# Thermostat.net
KiCad netlist of a schematic drawn in EAGLE
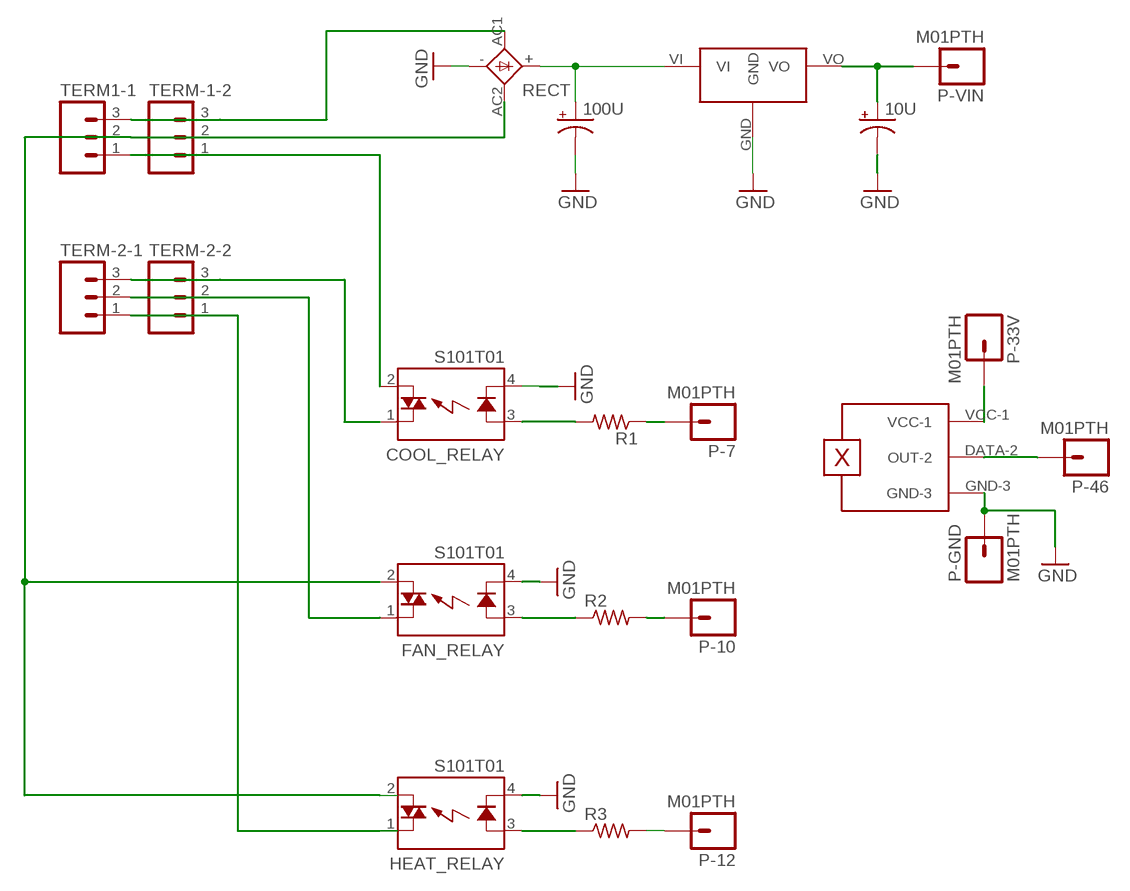
[diagram p0: schematic, sheet 1]

(export (version "E")
  (design (tool "Eeschema 10.0.6"))
  (components
    (comp (ref "10U")
      (value "CAP_POLPTH2")
      (footprint "eagle-import:CPOL-RADIAL-10UF-25V")
      (libsource (lib "eagle-import") (part "CAP_POLPTH2"))
    )
    (comp (ref "100U")
      (value "CAP_POLPTH1")
      (footprint "eagle-import:CPOL-RADIAL-100UF-25V")
      (libsource (lib "eagle-import") (part "CAP_POLPTH1"))
    )
    (comp (ref "COOL_RELAY")
      (value "S101T01")
      (footprint "eagle-import:S102T0X")
      (fields (field (name "OC_FARNELL") "unknown") (field (name "OC_NEWARK") "unknown"))
      (libsource (lib "eagle-import") (part "S?101T01"))
    )
    (comp (ref "FAN_RELAY")
      (value "S101T01")
      (footprint "eagle-import:S102T0X")
      (fields (field (name "OC_FARNELL") "unknown") (field (name "OC_NEWARK") "unknown"))
      (libsource (lib "eagle-import") (part "S?101T01"))
    )
    (comp (ref "HEAT_RELAY")
      (value "S101T01")
      (footprint "eagle-import:S102T0X")
      (fields (field (name "OC_FARNELL") "unknown") (field (name "OC_NEWARK") "unknown"))
      (libsource (lib "eagle-import") (part "S?101T01"))
    )
    (comp (ref "P-7")
      (value "M01PTH")
      (footprint "eagle-import:1X01")
      (libsource (lib "eagle-import") (part "M01PTH"))
    )
    (comp (ref "P-10")
      (value "M01PTH")
      (footprint "eagle-import:1X01")
      (libsource (lib "eagle-import") (part "M01PTH"))
    )
    (comp (ref "P-12")
      (value "M01PTH")
      (footprint "eagle-import:1X01")
      (libsource (lib "eagle-import") (part "M01PTH"))
    )
    (comp (ref "P-33V")
      (value "M01PTH")
      (footprint "eagle-import:1X01")
      (libsource (lib "eagle-import") (part "M01PTH"))
    )
    (comp (ref "P-46")
      (value "M01PTH")
      (footprint "eagle-import:1X01")
      (libsource (lib "eagle-import") (part "M01PTH"))
    )
    (comp (ref "P-GND")
      (value "M01PTH")
      (footprint "eagle-import:1X01")
      (libsource (lib "eagle-import") (part "M01PTH"))
    )
    (comp (ref "P-VIN")
      (value "M01PTH")
      (footprint "eagle-import:1X01")
      (libsource (lib "eagle-import") (part "M01PTH"))
    )
    (comp (ref "R1")
      (value "R-US_0204/2V")
      (footprint "eagle-import:0204V")
      (libsource (lib "eagle-import") (part "R-US_0204/2V"))
    )
    (comp (ref "R2")
      (value "R-US_0204/2V")
      (footprint "eagle-import:0204V")
      (libsource (lib "eagle-import") (part "R-US_0204/2V"))
    )
    (comp (ref "R3")
      (value "R-US_0204/2V")
      (footprint "eagle-import:0204V")
      (libsource (lib "eagle-import") (part "R-US_0204/2V"))
    )
    (comp (ref "RECT")
      (value "GBU4")
      (footprint "eagle-import:GBU4S")
      (libsource (lib "eagle-import") (part "GBU4"))
    )
    (comp (ref "TERM-1-2")
      (value "M031X03_NO_SILK")
      (footprint "eagle-import:1X03_NO_SILK")
      (libsource (lib "eagle-import") (part "M031X03_NO_SILK"))
    )
    (comp (ref "TERM-2-1")
      (value "M031X03_NO_SILK")
      (footprint "eagle-import:1X03_NO_SILK")
      (libsource (lib "eagle-import") (part "M031X03_NO_SILK"))
    )
    (comp (ref "TERM-2-2")
      (value "M031X03_NO_SILK")
      (footprint "eagle-import:1X03_NO_SILK")
      (libsource (lib "eagle-import") (part "M031X03_NO_SILK"))
    )
    (comp (ref "TERM1-1")
      (value "M031X03_NO_SILK")
      (footprint "eagle-import:1X03_NO_SILK")
      (libsource (lib "eagle-import") (part "M031X03_NO_SILK"))
    )
    (comp (ref "U$1")
      (value "TMP36")
      (footprint "eagle-import:TMP36")
      (libsource (lib "eagle-import") (part "TMP36"))
    )
    (comp (ref "U$2")
      (value "V715W-500R")
      (footprint "eagle-import:SWITCHINGREGULATOR")
      (libsource (lib "eagle-import") (part "V715W-500R"))
    )
  )
  (nets
    (net (code "1") (name "GND") (class "Default")
      (node (ref "100U") (pin "2") (pinfunction "-_2") (pintype "passive"))
      (node (ref "10U") (pin "2") (pinfunction "-_2") (pintype "passive"))
      (node (ref "COOL_RELAY") (pin "4") (pinfunction "K_4") (pintype "passive"))
      (node (ref "FAN_RELAY") (pin "4") (pinfunction "K_4") (pintype "passive"))
      (node (ref "HEAT_RELAY") (pin "4") (pinfunction "K_4") (pintype "passive"))
      (node (ref "P-GND") (pin "1") (pinfunction "1_1") (pintype "passive"))
      (node (ref "RECT") (pin "-") (pinfunction "-_-") (pintype "passive"))
      (node (ref "U$1") (pin "GND-3") (pinfunction "GND-3_GND-3") (pintype "bidirectional"))
      (node (ref "U$2") (pin "GND") (pinfunction "GND_GND") (pintype "bidirectional"))
    )
    (net (code "2") (name "Net-(10U-+)") (class "Default")
      (node (ref "10U") (pin "1") (pinfunction "+_1") (pintype "passive"))
      (node (ref "P-VIN") (pin "1") (pinfunction "1_1") (pintype "passive"))
      (node (ref "U$2") (pin "VO") (pinfunction "VO_VO") (pintype "bidirectional"))
    )
    (net (code "3") (name "Net-(100U-+)") (class "Default")
      (node (ref "100U") (pin "1") (pinfunction "+_1") (pintype "passive"))
      (node (ref "RECT") (pin "+") (pinfunction "+_+") (pintype "passive"))
      (node (ref "U$2") (pin "VI") (pinfunction "VI_VI") (pintype "bidirectional"))
    )
    (net (code "4") (name "Net-(COOL_RELAY-A)") (class "Default")
      (node (ref "COOL_RELAY") (pin "3") (pinfunction "A_3") (pintype "passive"))
      (node (ref "R1") (pin "2") (pinfunction "2_2") (pintype "passive"))
    )
    (net (code "5") (name "Net-(COOL_RELAY-DS1)") (class "Default")
      (node (ref "COOL_RELAY") (pin "1") (pinfunction "DS1_1") (pintype "passive"))
      (node (ref "TERM-2-1") (pin "3") (pinfunction "3_3") (pintype "passive"))
      (node (ref "TERM-2-2") (pin "3") (pinfunction "3_3") (pintype "passive"))
    )
    (net (code "6") (name "Net-(COOL_RELAY-DS2)") (class "Default")
      (node (ref "COOL_RELAY") (pin "2") (pinfunction "DS2_2") (pintype "passive"))
      (node (ref "TERM-1-2") (pin "1") (pinfunction "1_1") (pintype "passive"))
      (node (ref "TERM1-1") (pin "1") (pinfunction "1_1") (pintype "passive"))
    )
    (net (code "7") (name "Net-(FAN_RELAY-A)") (class "Default")
      (node (ref "FAN_RELAY") (pin "3") (pinfunction "A_3") (pintype "passive"))
      (node (ref "R2") (pin "1") (pinfunction "1_1") (pintype "passive"))
    )
    (net (code "8") (name "Net-(FAN_RELAY-DS1)") (class "Default")
      (node (ref "FAN_RELAY") (pin "1") (pinfunction "DS1_1") (pintype "passive"))
      (node (ref "TERM-2-1") (pin "2") (pinfunction "2_2") (pintype "passive"))
      (node (ref "TERM-2-2") (pin "2") (pinfunction "2_2") (pintype "passive"))
    )
    (net (code "9") (name "Net-(FAN_RELAY-DS2)") (class "Default")
      (node (ref "FAN_RELAY") (pin "2") (pinfunction "DS2_2") (pintype "passive"))
      (node (ref "HEAT_RELAY") (pin "2") (pinfunction "DS2_2") (pintype "passive"))
      (node (ref "RECT") (pin "AC2") (pinfunction "AC1_AC2") (pintype "passive"))
      (node (ref "TERM-1-2") (pin "2") (pinfunction "2_2") (pintype "passive"))
      (node (ref "TERM1-1") (pin "2") (pinfunction "2_2") (pintype "passive"))
    )
    (net (code "10") (name "Net-(HEAT_RELAY-A)") (class "Default")
      (node (ref "HEAT_RELAY") (pin "3") (pinfunction "A_3") (pintype "passive"))
      (node (ref "R3") (pin "1") (pinfunction "1_1") (pintype "passive"))
    )
    (net (code "11") (name "Net-(HEAT_RELAY-DS1)") (class "Default")
      (node (ref "HEAT_RELAY") (pin "1") (pinfunction "DS1_1") (pintype "passive"))
      (node (ref "TERM-2-1") (pin "1") (pinfunction "1_1") (pintype "passive"))
      (node (ref "TERM-2-2") (pin "1") (pinfunction "1_1") (pintype "passive"))
    )
    (net (code "12") (name "Net-(P-7-Pad1)") (class "Default")
      (node (ref "P-7") (pin "1") (pinfunction "1_1") (pintype "passive"))
      (node (ref "R1") (pin "1") (pinfunction "1_1") (pintype "passive"))
    )
    (net (code "13") (name "Net-(P-10-Pad1)") (class "Default")
      (node (ref "P-10") (pin "1") (pinfunction "1_1") (pintype "passive"))
      (node (ref "R2") (pin "2") (pinfunction "2_2") (pintype "passive"))
    )
    (net (code "14") (name "Net-(P-12-Pad1)") (class "Default")
      (node (ref "P-12") (pin "1") (pinfunction "1_1") (pintype "passive"))
      (node (ref "R3") (pin "2") (pinfunction "2_2") (pintype "passive"))
    )
    (net (code "15") (name "Net-(P-33V-Pad1)") (class "Default")
      (node (ref "P-33V") (pin "1") (pinfunction "1_1") (pintype "passive"))
      (node (ref "U$1") (pin "VCC-1") (pinfunction "VCC-1_VCC-1") (pintype "bidirectional"))
    )
    (net (code "16") (name "Net-(RECT-AC2)") (class "Default")
      (node (ref "RECT") (pin "AC1") (pinfunction "AC2_AC1") (pintype "passive"))
      (node (ref "TERM-1-2") (pin "3") (pinfunction "3_3") (pintype "passive"))
      (node (ref "TERM1-1") (pin "3") (pinfunction "3_3") (pintype "passive"))
    )
    (net (code "17") (name "Net-(U$1-OUT-2)") (class "Default")
      (node (ref "P-46") (pin "1") (pinfunction "1_1") (pintype "passive"))
      (node (ref "U$1") (pin "DATA-2") (pinfunction "OUT-2_DATA-2") (pintype "bidirectional"))
    )
  )
)
